# Sheet5_Pin_Headers.net
KiCad netlist of a schematic drawn in Altium Designer
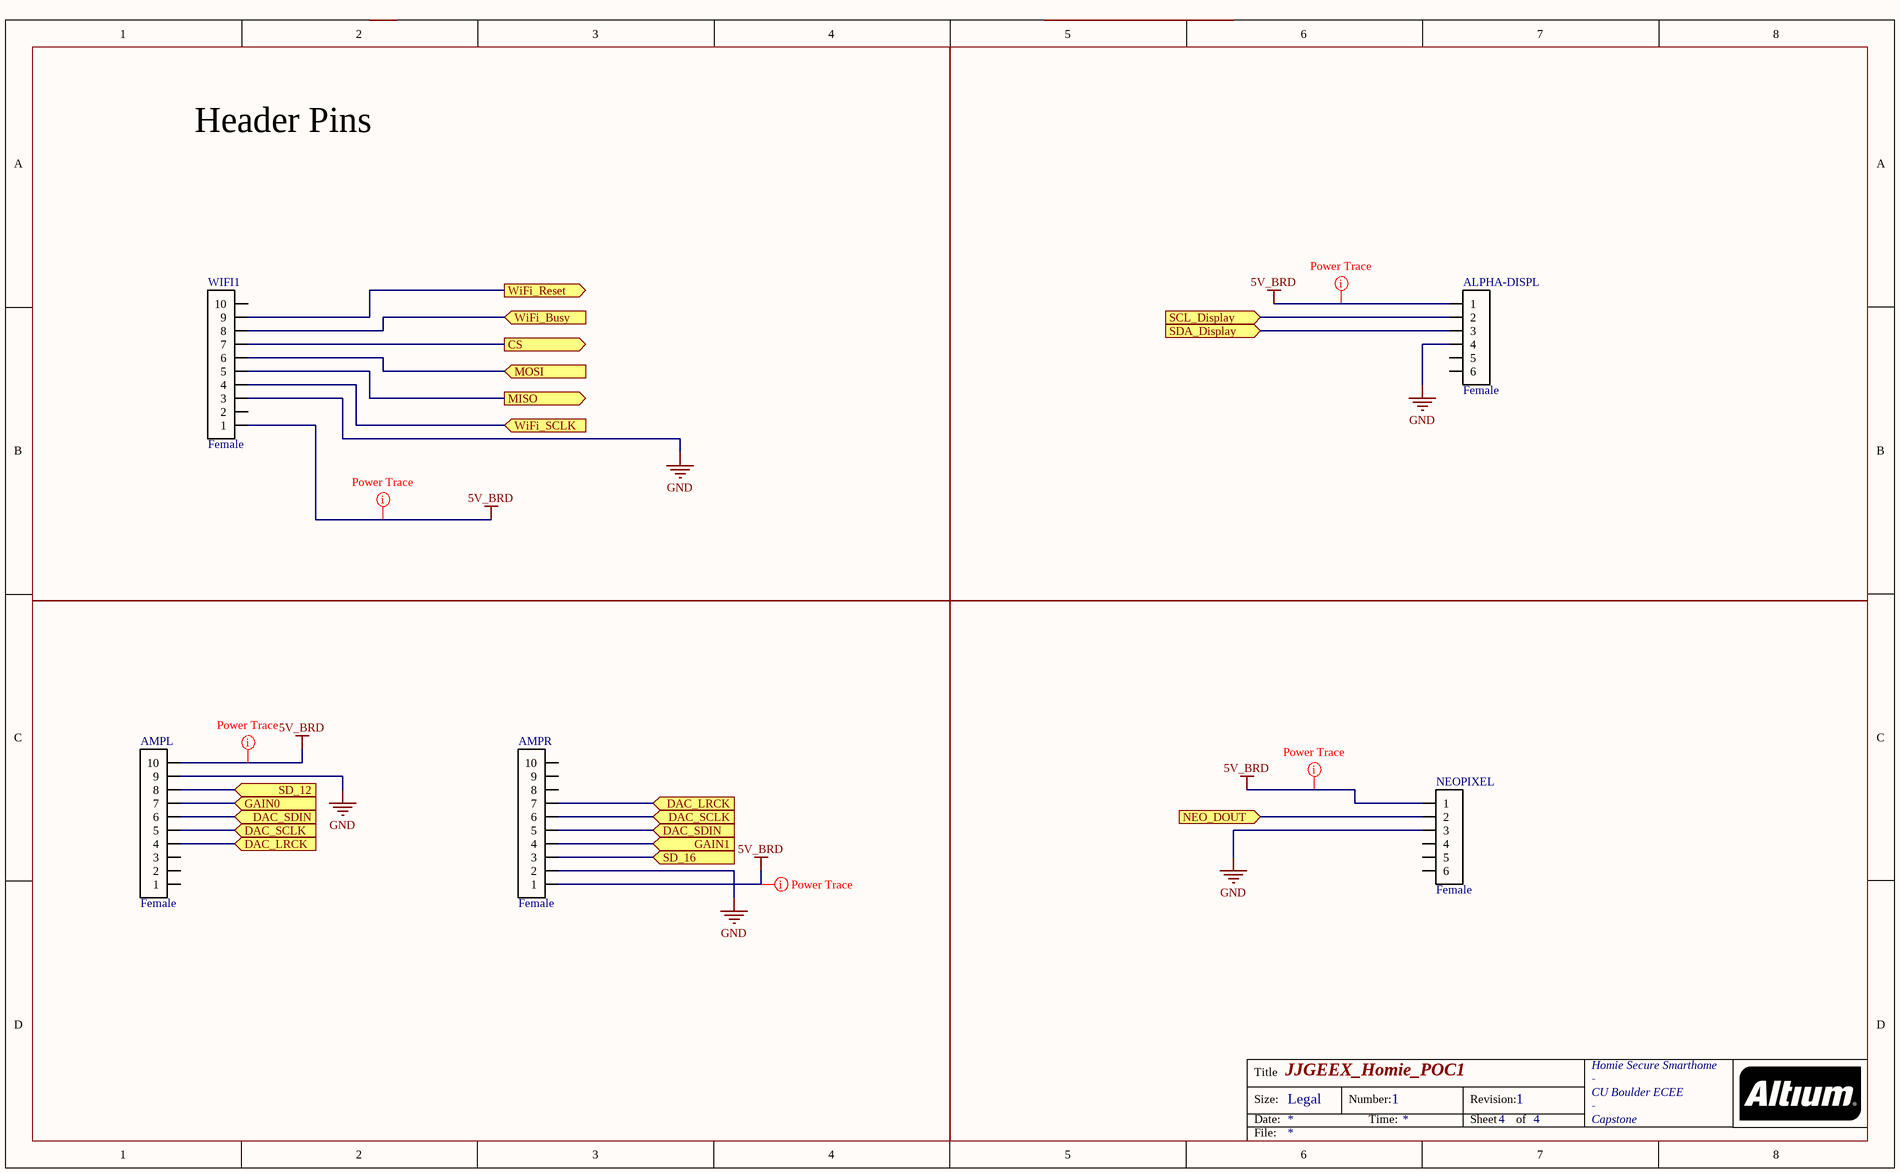
[diagram p0: Sheet5_Pin_Headers.SchDoc]

(export (version "E")
  (design (tool "Eeschema 10.0.6"))
  (components
    (comp (ref "ALPHA-DISPL")
      (value "Female")
      (footprint "6_PIN_100MIL")
      (description "6 Position Header Connector 0.100\" (2.54mm) Through Hole Tin")
      (fields (field (name "DIGIKEY PART") "S7004-ND") (field (name "Comment") "PPTC061LFBN-RC"))
      (libsource (lib "ECEN5730Lib_2020_09_AR") (part "JF_6_PIN_FEMALE"))
    )
    (comp (ref "AMPL")
      (value "Female")
      (footprint "10_PIN_100MIL")
      (description "10 Position Header Connector 0.100\" (2.54mm) Through Hole Tin")
      (fields (field (name "DIGIKEY PART") "S7008-ND") (field (name "Comment") "PPTC101LFBN-RC"))
      (libsource (lib "ECEN5730Lib_2020_09_AR") (part "JF_10_PIN_FEMALE"))
    )
    (comp (ref "AMPR")
      (value "Female")
      (footprint "10_PIN_100MIL")
      (description "10 Position Header Connector 0.100\" (2.54mm) Through Hole Tin")
      (fields (field (name "DIGIKEY PART") "S7008-ND") (field (name "Comment") "PPTC101LFBN-RC"))
      (libsource (lib "ECEN5730Lib_2020_09_AR") (part "JF_10_PIN_FEMALE"))
    )
    (comp (ref "NEOPIXEL")
      (value "Female")
      (footprint "6_PIN_100MIL")
      (description "6 Position Header Connector 0.100\" (2.54mm) Through Hole Tin")
      (fields (field (name "DIGIKEY PART") "S7004-ND") (field (name "Comment") "PPTC061LFBN-RC"))
      (libsource (lib "ECEN5730Lib_2020_09_AR") (part "JF_6_PIN_FEMALE"))
    )
    (comp (ref "WIFI1")
      (value "Female")
      (footprint "10_PIN_100MIL")
      (description "10 Position Header Connector 0.100\" (2.54mm) Through Hole Tin")
      (fields (field (name "DIGIKEY PART") "S7008-ND") (field (name "Comment") "PPTC101LFBN-RC"))
      (libsource (lib "ECEN5730Lib_2020_09_AR") (part "JF_10_PIN_FEMALE"))
    )
  )
  (nets
    (net (code "1") (name "/CS") (class "Default")
      (node (ref "WIFI1") (pin "7") (pinfunction "7_7") (pintype "passive"))
    )
    (net (code "2") (name "/DAC_LRCK") (class "Default")
      (node (ref "AMPL") (pin "4") (pinfunction "4_4") (pintype "passive"))
      (node (ref "AMPR") (pin "7") (pinfunction "7_7") (pintype "passive"))
    )
    (net (code "3") (name "/DAC_SCLK") (class "Default")
      (node (ref "AMPL") (pin "5") (pinfunction "5_5") (pintype "passive"))
      (node (ref "AMPR") (pin "6") (pinfunction "6_6") (pintype "passive"))
    )
    (net (code "4") (name "/DAC_SDIN") (class "Default")
      (node (ref "AMPL") (pin "6") (pinfunction "6_6") (pintype "passive"))
      (node (ref "AMPR") (pin "5") (pinfunction "5_5") (pintype "passive"))
    )
    (net (code "5") (name "/GAIN0") (class "Default")
      (node (ref "AMPL") (pin "7") (pinfunction "7_7") (pintype "passive"))
    )
    (net (code "6") (name "/GAIN1") (class "Default")
      (node (ref "AMPR") (pin "4") (pinfunction "4_4") (pintype "passive"))
    )
    (net (code "7") (name "/MISO") (class "Default")
      (node (ref "WIFI1") (pin "5") (pinfunction "5_5") (pintype "passive"))
    )
    (net (code "8") (name "/MOSI") (class "Default")
      (node (ref "WIFI1") (pin "6") (pinfunction "6_6") (pintype "passive"))
    )
    (net (code "9") (name "/NEO_DOUT") (class "Default")
      (node (ref "NEOPIXEL") (pin "2") (pinfunction "2_2") (pintype "passive"))
    )
    (net (code "10") (name "/SCL_Display") (class "Default")
      (node (ref "ALPHA-DISPL") (pin "2") (pinfunction "2_2") (pintype "passive"))
    )
    (net (code "11") (name "/SDA_Display") (class "Default")
      (node (ref "ALPHA-DISPL") (pin "3") (pinfunction "3_3") (pintype "passive"))
    )
    (net (code "12") (name "/SD_12") (class "Default")
      (node (ref "AMPL") (pin "8") (pinfunction "8_8") (pintype "passive"))
    )
    (net (code "13") (name "/SD_16") (class "Default")
      (node (ref "AMPR") (pin "3") (pinfunction "3_3") (pintype "passive"))
    )
    (net (code "14") (name "/WiFi_Busy") (class "Default")
      (node (ref "WIFI1") (pin "8") (pinfunction "8_8") (pintype "passive"))
    )
    (net (code "15") (name "/WiFi_Reset") (class "Default")
      (node (ref "WIFI1") (pin "9") (pinfunction "9_9") (pintype "passive"))
    )
    (net (code "16") (name "/WiFi_SCLK") (class "Default")
      (node (ref "WIFI1") (pin "4") (pinfunction "4_4") (pintype "passive"))
    )
    (net (code "17") (name "5V_BRD") (class "Default")
      (node (ref "ALPHA-DISPL") (pin "1") (pinfunction "1_1") (pintype "passive"))
      (node (ref "AMPL") (pin "10") (pinfunction "10_10") (pintype "passive"))
      (node (ref "AMPR") (pin "1") (pinfunction "1_1") (pintype "passive"))
      (node (ref "NEOPIXEL") (pin "1") (pinfunction "1_1") (pintype "passive"))
      (node (ref "WIFI1") (pin "1") (pinfunction "1_1") (pintype "passive"))
    )
    (net (code "18") (name "GND") (class "Default")
      (node (ref "ALPHA-DISPL") (pin "4") (pinfunction "4_4") (pintype "passive"))
      (node (ref "AMPL") (pin "9") (pinfunction "9_9") (pintype "passive"))
      (node (ref "AMPR") (pin "2") (pinfunction "2_2") (pintype "passive"))
      (node (ref "NEOPIXEL") (pin "3") (pinfunction "3_3") (pintype "passive"))
      (node (ref "WIFI1") (pin "3") (pinfunction "3_3") (pintype "passive"))
    )
    (net (code "19") (name "unconnected-(ALPHA-DISPL-Pad5)") (class "Default")
      (node (ref "ALPHA-DISPL") (pin "5") (pinfunction "5_5") (pintype "passive"))
    )
    (net (code "20") (name "unconnected-(ALPHA-DISPL-Pad6)") (class "Default")
      (node (ref "ALPHA-DISPL") (pin "6") (pinfunction "6_6") (pintype "passive"))
    )
    (net (code "21") (name "unconnected-(AMPL-Pad1)") (class "Default")
      (node (ref "AMPL") (pin "1") (pinfunction "1_1") (pintype "passive"))
    )
    (net (code "22") (name "unconnected-(AMPL-Pad2)") (class "Default")
      (node (ref "AMPL") (pin "2") (pinfunction "2_2") (pintype "passive"))
    )
    (net (code "23") (name "unconnected-(AMPL-Pad3)") (class "Default")
      (node (ref "AMPL") (pin "3") (pinfunction "3_3") (pintype "passive"))
    )
    (net (code "24") (name "unconnected-(AMPR-Pad8)") (class "Default")
      (node (ref "AMPR") (pin "8") (pinfunction "8_8") (pintype "passive"))
    )
    (net (code "25") (name "unconnected-(AMPR-Pad9)") (class "Default")
      (node (ref "AMPR") (pin "9") (pinfunction "9_9") (pintype "passive"))
    )
    (net (code "26") (name "unconnected-(AMPR-Pad10)") (class "Default")
      (node (ref "AMPR") (pin "10") (pinfunction "10_10") (pintype "passive"))
    )
    (net (code "27") (name "unconnected-(NEOPIXEL-Pad4)") (class "Default")
      (node (ref "NEOPIXEL") (pin "4") (pinfunction "4_4") (pintype "passive"))
    )
    (net (code "28") (name "unconnected-(NEOPIXEL-Pad5)") (class "Default")
      (node (ref "NEOPIXEL") (pin "5") (pinfunction "5_5") (pintype "passive"))
    )
    (net (code "29") (name "unconnected-(NEOPIXEL-Pad6)") (class "Default")
      (node (ref "NEOPIXEL") (pin "6") (pinfunction "6_6") (pintype "passive"))
    )
    (net (code "30") (name "unconnected-(WIFI1-Pad2)") (class "Default")
      (node (ref "WIFI1") (pin "2") (pinfunction "2_2") (pintype "passive"))
    )
    (net (code "31") (name "unconnected-(WIFI1-Pad10)") (class "Default")
      (node (ref "WIFI1") (pin "10") (pinfunction "10_10") (pintype "passive"))
    )
  )
)
